# XR_Preamp.net
KiCad netlist of a schematic drawn in EAGLE
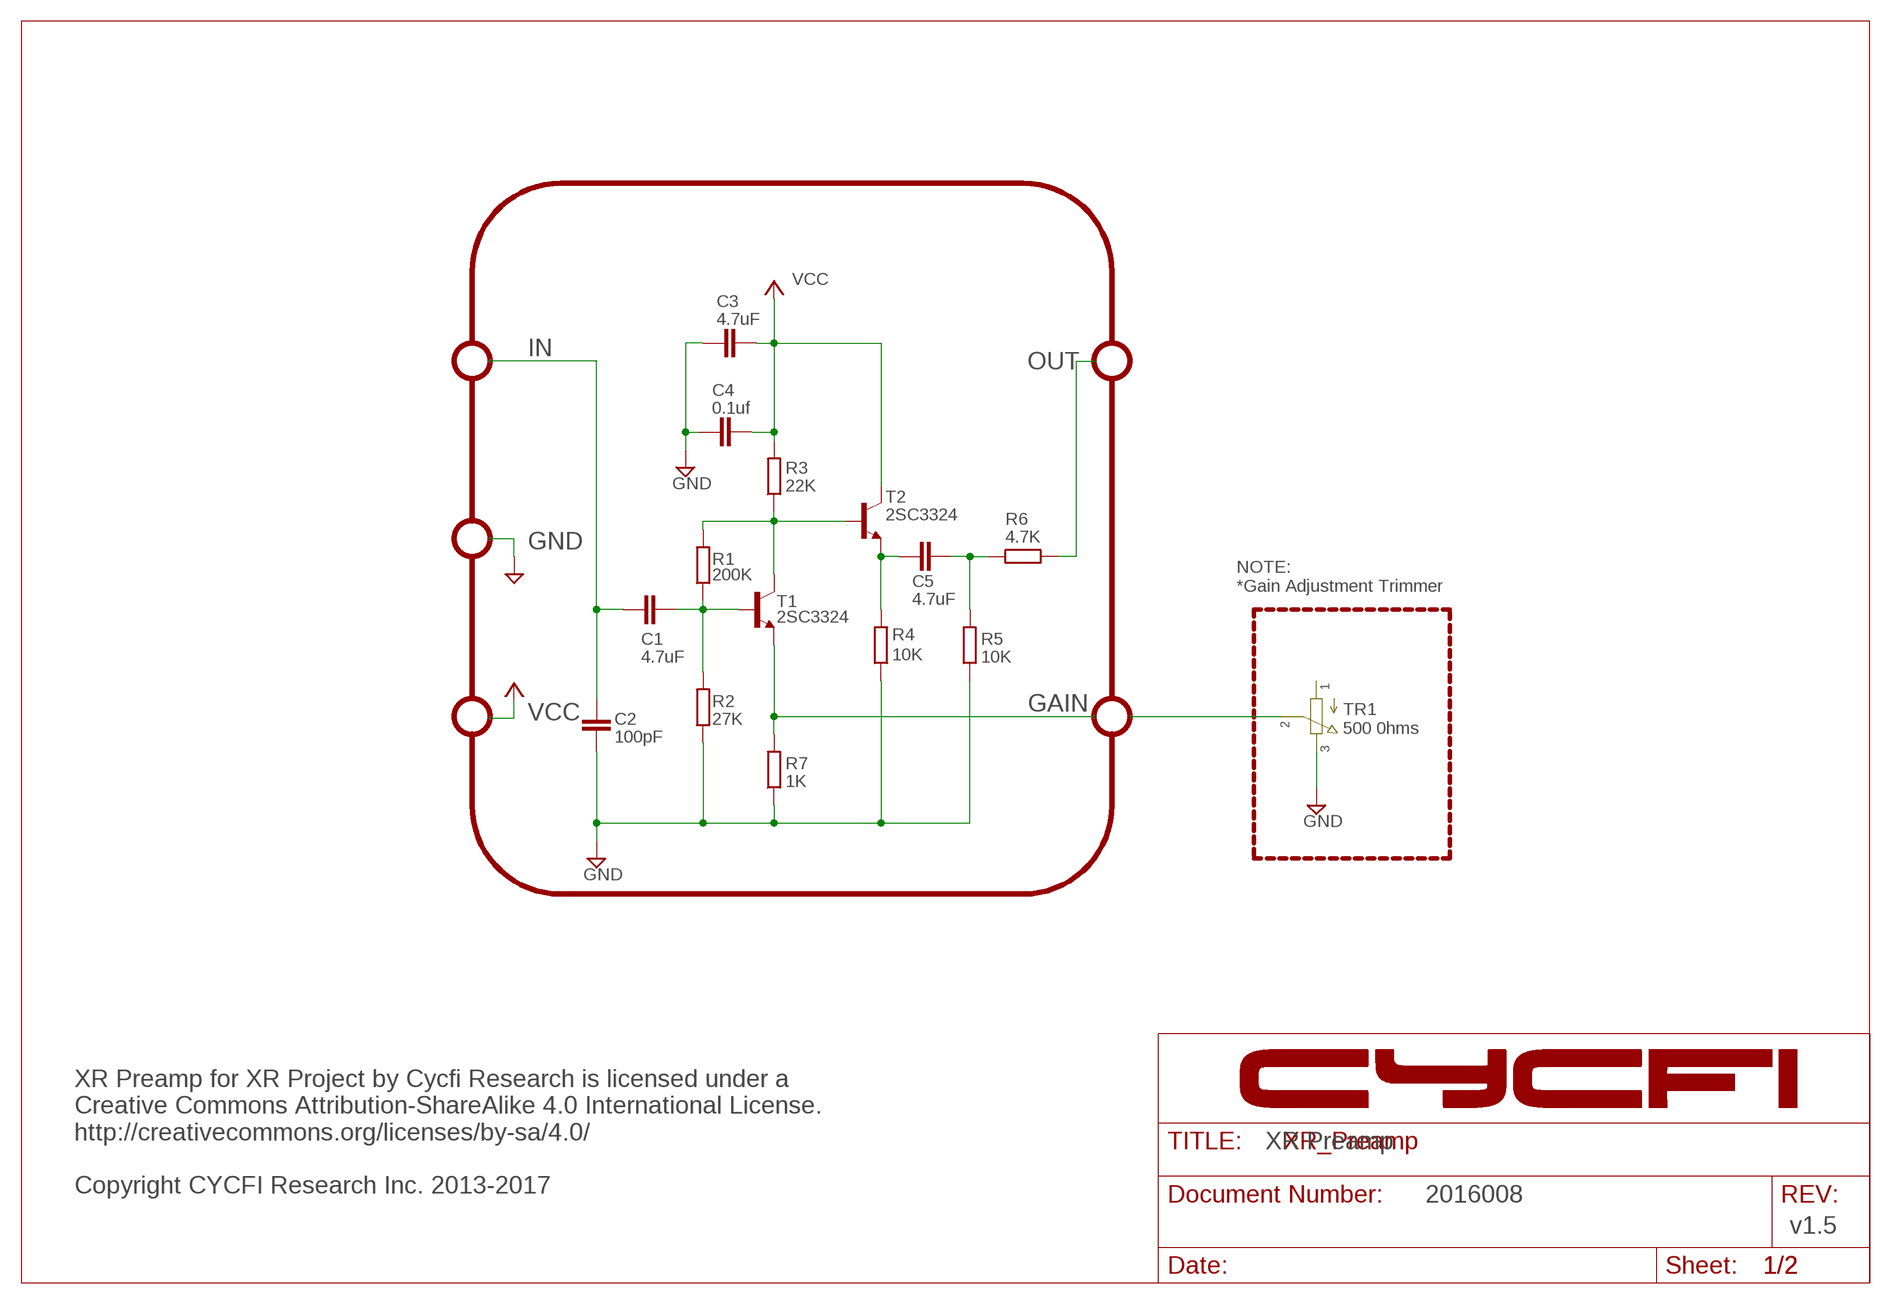
[diagram p0: schematic, sheet 1]
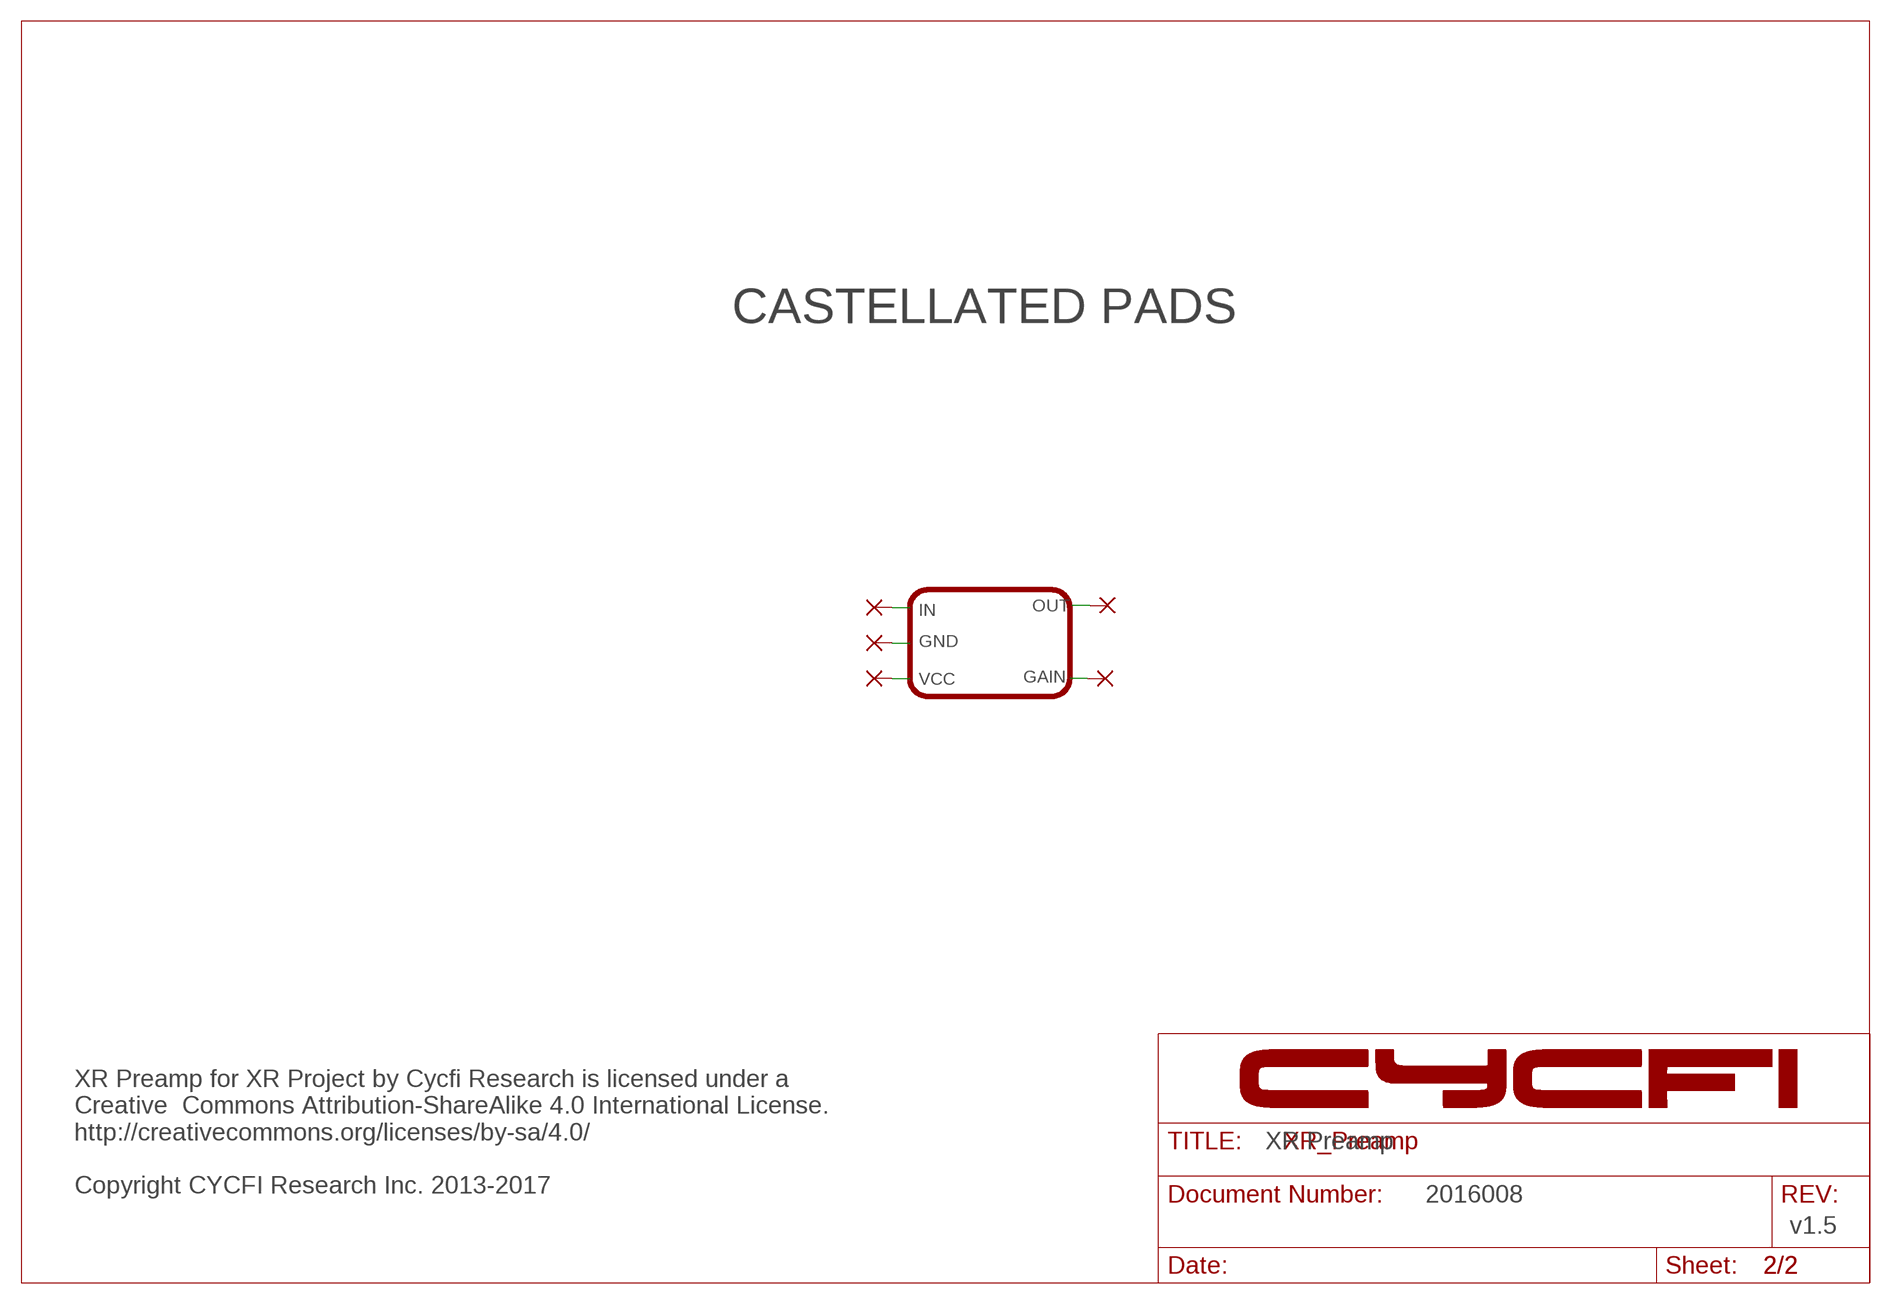
[diagram p1: schematic, sheet 2]

(export (version "E")
  (design (tool "Eeschema 10.0.6"))
  (components
    (comp (ref "PAD1")
      (value "WIREPAD2,15/1,0")
      (footprint "eagle-import:1,6_0,8")
      (libsource (lib "eagle-import") (part "1,6/0,8"))
    )
    (comp (ref "PAD2")
      (value "WIREPAD2,15/1,0")
      (footprint "eagle-import:1,6_0,8")
      (libsource (lib "eagle-import") (part "1,6/0,8"))
    )
    (comp (ref "PAD3")
      (value "WIREPAD2,15/1,0")
      (footprint "eagle-import:1,6_0,8")
      (libsource (lib "eagle-import") (part "1,6/0,8"))
    )
    (comp (ref "PAD4")
      (value "WIREPAD2,15/1,0")
      (footprint "eagle-import:1,6_0,8")
      (libsource (lib "eagle-import") (part "1,6/0,8"))
    )
    (comp (ref "PAD5")
      (value "WIREPAD2,15/1,0")
      (footprint "eagle-import:1,6_0,8")
      (libsource (lib "eagle-import") (part "1,6/0,8"))
    )
    (comp (ref "C1")
      (value "4.7uF")
      (footprint "eagle-import:C0603")
      (libsource (lib "eagle-import") (part "C-EUC0603"))
    )
    (comp (ref "C2")
      (value "100pF")
      (footprint "eagle-import:C0402")
      (libsource (lib "eagle-import") (part "C-EUC0402"))
    )
    (comp (ref "C3")
      (value "4.7uF")
      (footprint "eagle-import:C0603")
      (libsource (lib "eagle-import") (part "C-EUC0603"))
    )
    (comp (ref "C4")
      (value "0.1uf")
      (footprint "eagle-import:C0402")
      (libsource (lib "eagle-import") (part "C-EUC0402"))
    )
    (comp (ref "C5")
      (value "4.7uF")
      (footprint "eagle-import:C0402")
      (libsource (lib "eagle-import") (part "C-EUC0402"))
    )
    (comp (ref "R1")
      (value "200K")
      (footprint "eagle-import:R0402")
      (libsource (lib "eagle-import") (part "R-EU_R0402"))
    )
    (comp (ref "R2")
      (value "27K")
      (footprint "eagle-import:R0402")
      (libsource (lib "eagle-import") (part "R-EU_R0402"))
    )
    (comp (ref "R3")
      (value "22K")
      (footprint "eagle-import:R0402")
      (libsource (lib "eagle-import") (part "R-EU_R0402"))
    )
    (comp (ref "R4")
      (value "10K")
      (footprint "eagle-import:R0402")
      (libsource (lib "eagle-import") (part "R-EU_R0402"))
    )
    (comp (ref "R5")
      (value "10K")
      (footprint "eagle-import:R0402")
      (libsource (lib "eagle-import") (part "R-EU_R0402"))
    )
    (comp (ref "R6")
      (value "4.7K")
      (footprint "eagle-import:R0402")
      (libsource (lib "eagle-import") (part "R-EU_R0402"))
    )
    (comp (ref "R7")
      (value "1K")
      (footprint "eagle-import:R0402")
      (libsource (lib "eagle-import") (part "R-EU_R0402"))
    )
    (comp (ref "T1")
      (value "2SC3324")
      (footprint "eagle-import:SOT23")
      (libsource (lib "eagle-import") (part "BC846"))
    )
    (comp (ref "T2")
      (value "2SC3324")
      (footprint "eagle-import:SOT23")
      (libsource (lib "eagle-import") (part "BC846"))
    )
  )
  (nets
    (net (code "1") (name "GAIN") (class "Default")
      (node (ref "PAD1") (pin "1") (pinfunction "P_1") (pintype "passive"))
      (node (ref "R7") (pin "2") (pinfunction "2_2") (pintype "passive"))
      (node (ref "T1") (pin "2") (pinfunction "E_2") (pintype "passive"))
    )
    (net (code "2") (name "GND") (class "Default")
      (node (ref "C2") (pin "1") (pinfunction "1_1") (pintype "passive"))
      (node (ref "C3") (pin "1") (pinfunction "1_1") (pintype "passive"))
      (node (ref "C4") (pin "1") (pinfunction "1_1") (pintype "passive"))
      (node (ref "PAD2") (pin "1") (pinfunction "P_1") (pintype "passive"))
      (node (ref "R2") (pin "1") (pinfunction "1_1") (pintype "passive"))
      (node (ref "R4") (pin "1") (pinfunction "1_1") (pintype "passive"))
      (node (ref "R5") (pin "1") (pinfunction "1_1") (pintype "passive"))
      (node (ref "R7") (pin "1") (pinfunction "1_1") (pintype "passive"))
    )
    (net (code "3") (name "IN") (class "Default")
      (node (ref "C1") (pin "1") (pinfunction "1_1") (pintype "passive"))
      (node (ref "C2") (pin "2") (pinfunction "2_2") (pintype "passive"))
      (node (ref "PAD3") (pin "1") (pinfunction "P_1") (pintype "passive"))
    )
    (net (code "4") (name "Net-(C5-Pad1)") (class "Default")
      (node (ref "C5") (pin "1") (pinfunction "1_1") (pintype "passive"))
      (node (ref "R5") (pin "2") (pinfunction "2_2") (pintype "passive"))
      (node (ref "R6") (pin "1") (pinfunction "1_1") (pintype "passive"))
    )
    (net (code "5") (name "Net-(T1-B)") (class "Default")
      (node (ref "C1") (pin "2") (pinfunction "2_2") (pintype "passive"))
      (node (ref "R1") (pin "1") (pinfunction "1_1") (pintype "passive"))
      (node (ref "R2") (pin "2") (pinfunction "2_2") (pintype "passive"))
      (node (ref "T1") (pin "1") (pinfunction "B_1") (pintype "passive"))
    )
    (net (code "6") (name "Net-(T1-C)") (class "Default")
      (node (ref "R1") (pin "2") (pinfunction "2_2") (pintype "passive"))
      (node (ref "R3") (pin "1") (pinfunction "1_1") (pintype "passive"))
      (node (ref "T1") (pin "3") (pinfunction "C_3") (pintype "passive"))
      (node (ref "T2") (pin "1") (pinfunction "B_1") (pintype "passive"))
    )
    (net (code "7") (name "Net-(T2-E)") (class "Default")
      (node (ref "C5") (pin "2") (pinfunction "2_2") (pintype "passive"))
      (node (ref "R4") (pin "2") (pinfunction "2_2") (pintype "passive"))
      (node (ref "T2") (pin "2") (pinfunction "E_2") (pintype "passive"))
    )
    (net (code "8") (name "OUT") (class "Default")
      (node (ref "PAD5") (pin "1") (pinfunction "P_1") (pintype "passive"))
      (node (ref "R6") (pin "2") (pinfunction "2_2") (pintype "passive"))
    )
    (net (code "9") (name "VCC") (class "Default")
      (node (ref "C3") (pin "2") (pinfunction "2_2") (pintype "passive"))
      (node (ref "C4") (pin "2") (pinfunction "2_2") (pintype "passive"))
      (node (ref "PAD4") (pin "1") (pinfunction "P_1") (pintype "passive"))
      (node (ref "R3") (pin "2") (pinfunction "2_2") (pintype "passive"))
      (node (ref "T2") (pin "3") (pinfunction "C_3") (pintype "passive"))
    )
  )
)
